# BW1098FFC_Connector.net
KiCad netlist of a schematic drawn in Altium Designer
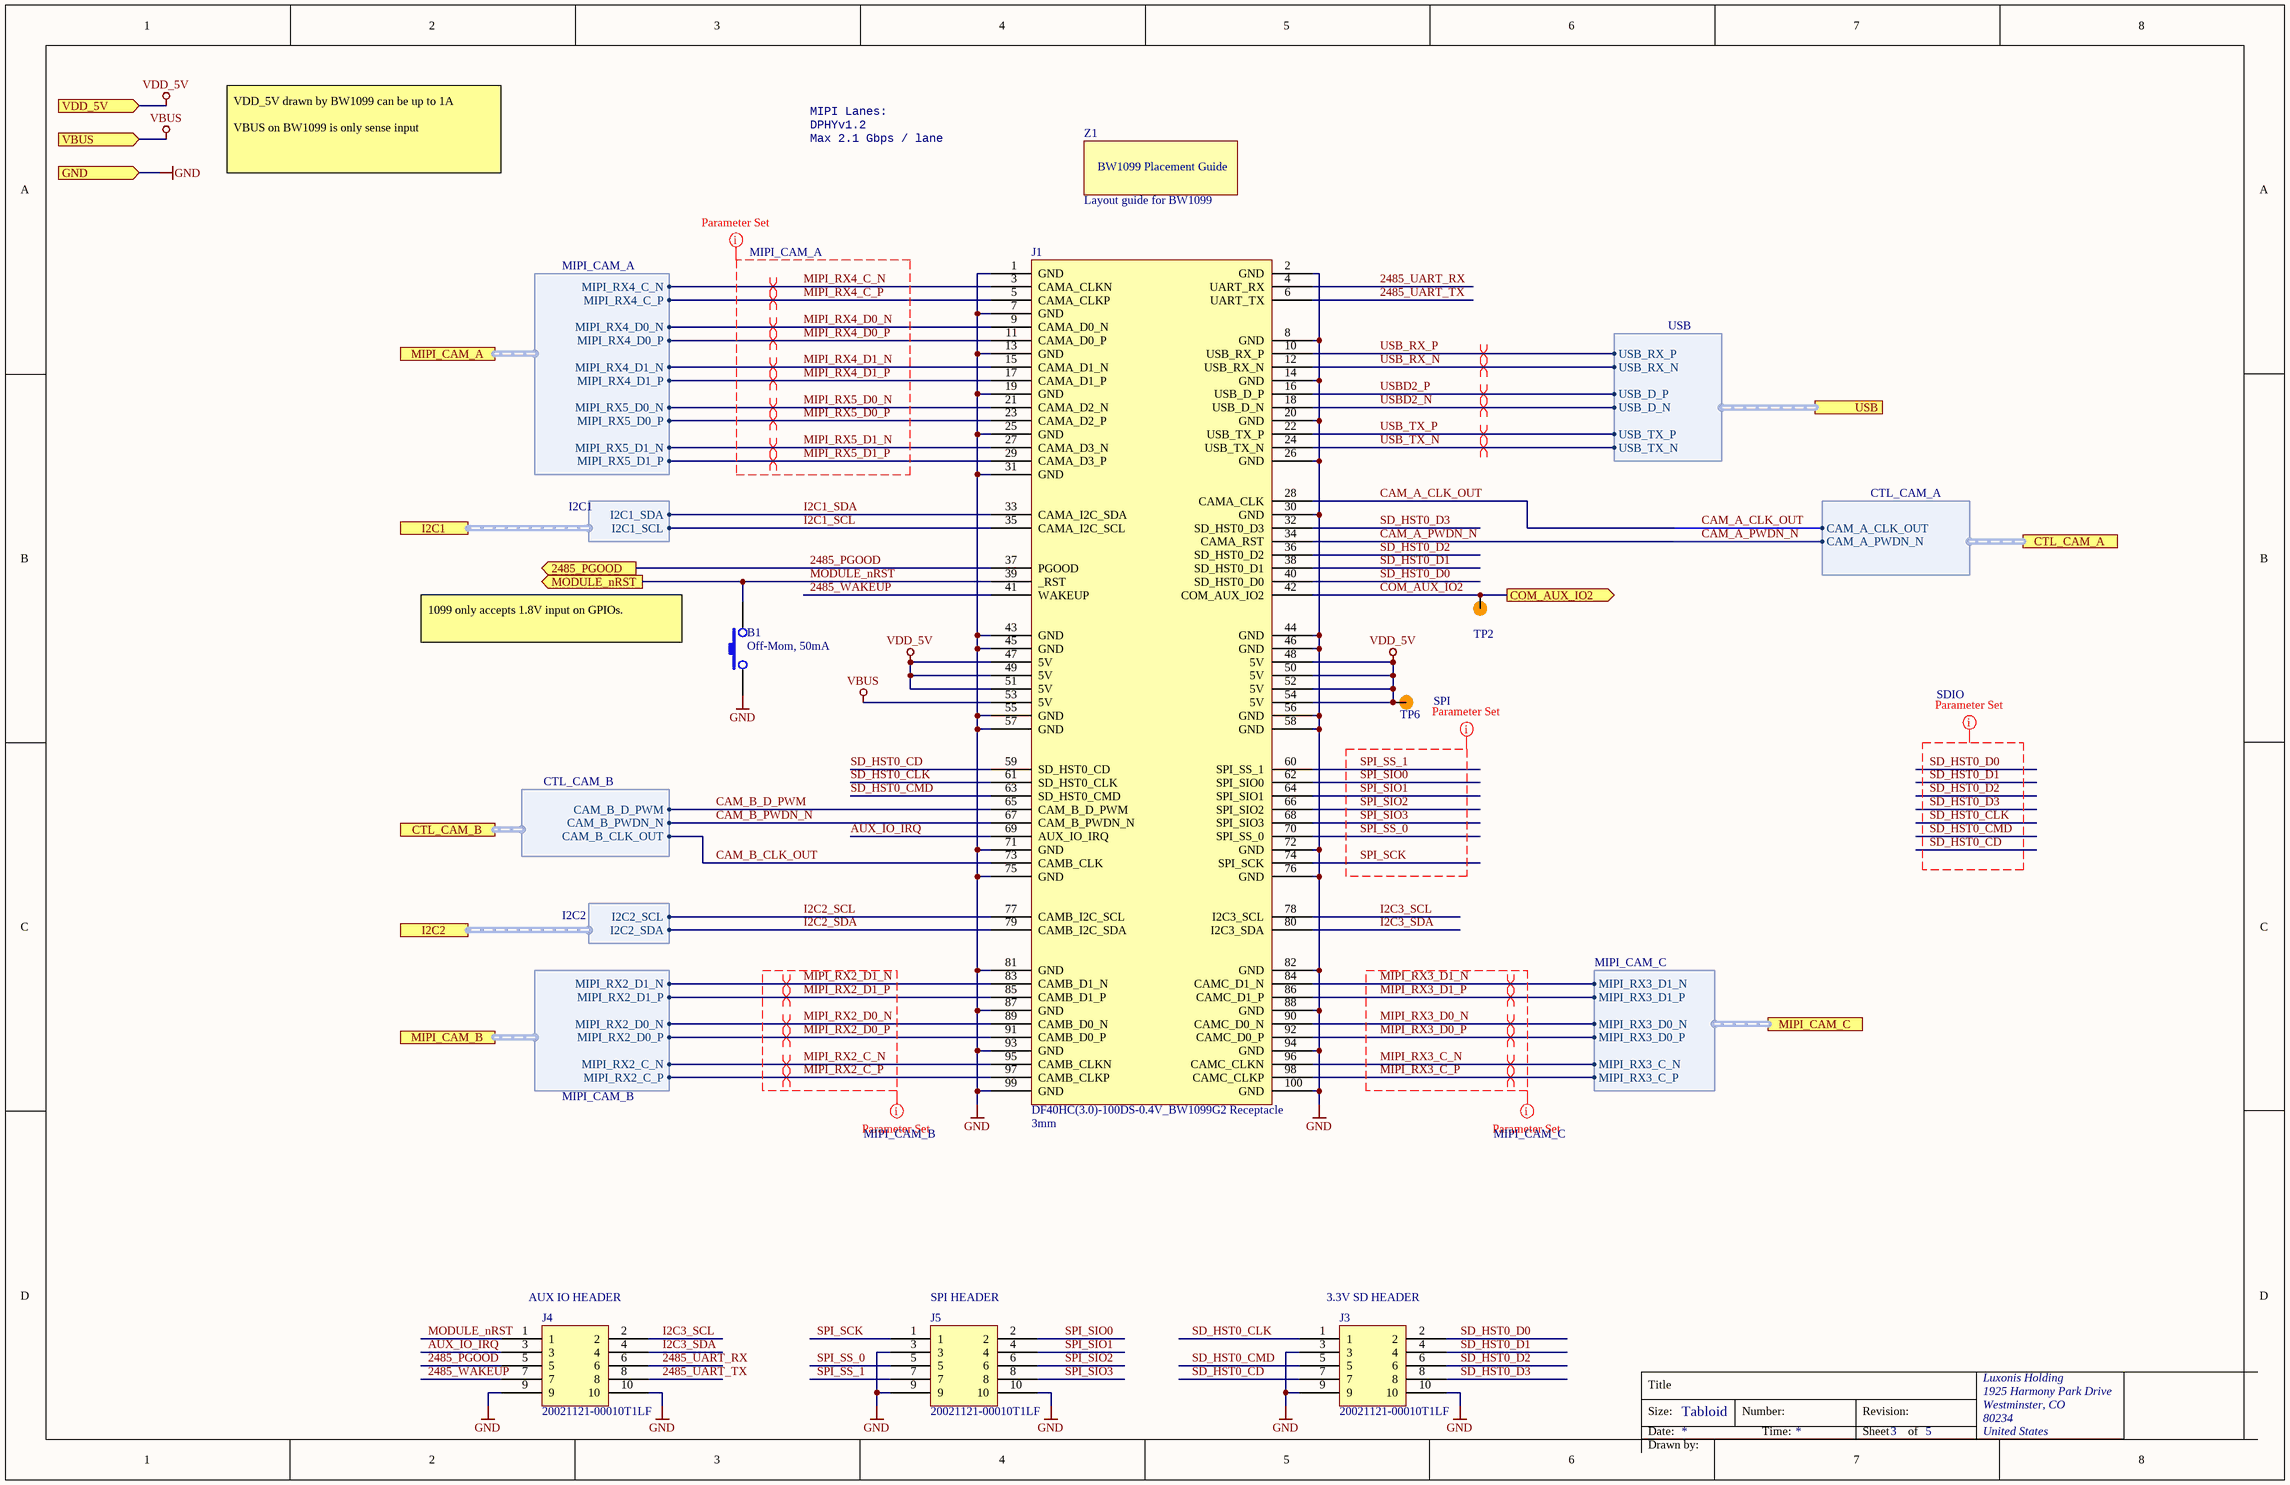
[diagram p0: BW1098FFC_Connector.SchDoc]

(export (version "E")
  (design (tool "Eeschema 10.0.6"))
  (components
    (comp (ref "B1")
      (value "Off-Mom, 50mA")
      (footprint "LuxonisMaster:DTSM-32N-V")
      (description "SWITCH TACTILE SMT 3.5mm * 6mm , brown 160gf")
      (libsource (lib "LuxonisMaster") (part "DTSM-32N-V"))
    )
    (comp (ref "J1")
      (value "DF40HC(3.0)-100DS-0.4V_BW1099G2 Receptacle")
      (footprint "LuxonisMaster:DF40HC-3.0-100DS-0.4V_minpad")
      (description "CONN RCPT 100POS 0.4MM SMD GOLD")
      (fields (field (name "MATED STACKING HEIGHT") "3mm"))
      (libsource (lib "LuxonisMaster") (part "DF40HC(3.0)-100DS-0.4V_BW1099_G2"))
    )
    (comp (ref "J3")
      (value "20021121-00010T1LF")
      (footprint "LuxonisMaster:20021121-00010T1LF")
      (description "CONN HEADER SMD 10POS 1.27MM")
      (libsource (lib "LuxonisMaster") (part "20021121-00010T1LF"))
    )
    (comp (ref "J4")
      (value "20021121-00010T1LF")
      (footprint "LuxonisMaster:20021121-00010T1LF")
      (description "CONN HEADER SMD 10POS 1.27MM")
      (libsource (lib "LuxonisMaster") (part "20021121-00010T1LF"))
    )
    (comp (ref "J5")
      (value "20021121-00010T1LF")
      (footprint "LuxonisMaster:20021121-00010T1LF")
      (description "CONN HEADER SMD 10POS 1.27MM")
      (libsource (lib "LuxonisMaster") (part "20021121-00010T1LF"))
    )
    (comp (ref "TP2")
      (value "TP100_200_NS")
      (footprint "LuxonisMaster:TP100_200_NS")
      (libsource (lib "LuxonisMaster") (part "TEST_POINT"))
    )
    (comp (ref "TP6")
      (value "TP100_200_NS")
      (footprint "LuxonisMaster:TP100_200_NS")
      (libsource (lib "LuxonisMaster") (part "TEST_POINT"))
    )
    (comp (ref "Z1")
      (value "Layout guide for BW1099")
      (footprint "LuxonisMaster:BW1099_Footprint")
      (description "MISC - Use for aligning BW1099 mount")
      (libsource (lib "LuxonisMaster") (part "BW1099_Footprint"))
    )
  )
  (nets
    (net (code "9") (name "/2485_PGOOD") (class "Default")
      (node (ref "J1") (pin "37") (pinfunction "PGOOD_37") (pintype "passive"))
      (node (ref "J4") (pin "5") (pinfunction "5_5") (pintype "passive"))
    )
    (net (code "10") (name "/2485_UART_RX") (class "Default")
      (node (ref "J1") (pin "4") (pinfunction "UART_RX_4") (pintype "passive"))
      (node (ref "J4") (pin "6") (pinfunction "6_6") (pintype "passive"))
    )
    (net (code "11") (name "/2485_UART_TX") (class "Default")
      (node (ref "J1") (pin "6") (pinfunction "UART_TX_6") (pintype "passive"))
      (node (ref "J4") (pin "8") (pinfunction "8_8") (pintype "passive"))
    )
    (net (code "12") (name "/2485_WAKEUP") (class "Default")
      (node (ref "J1") (pin "41") (pinfunction "WAKEUP_41") (pintype "passive"))
      (node (ref "J4") (pin "7") (pinfunction "7_7") (pintype "passive"))
    )
    (net (code "13") (name "/AUX_IO_IRQ") (class "Default")
      (node (ref "J1") (pin "69") (pinfunction "AUX_IO_IRQ_69") (pintype "passive"))
      (node (ref "J4") (pin "3") (pinfunction "3_3") (pintype "passive"))
    )
    (net (code "14") (name "/CAM_A_CLK_OUT") (class "Default")
      (node (ref "J1") (pin "28") (pinfunction "CAMA_CLK_28") (pintype "passive"))
    )
    (net (code "15") (name "/CAM_A_PWDN_N") (class "Default")
      (node (ref "J1") (pin "34") (pinfunction "CAMA_RST_34") (pintype "passive"))
    )
    (net (code "16") (name "/CAM_B_CLK_OUT") (class "Default")
      (node (ref "J1") (pin "73") (pinfunction "CAMB_CLK_73") (pintype "passive"))
    )
    (net (code "17") (name "/CAM_B_D_PWM") (class "Default")
      (node (ref "J1") (pin "65") (pinfunction "CAM_B_D_PWM_65") (pintype "passive"))
    )
    (net (code "18") (name "/CAM_B_PWDN_N") (class "Default")
      (node (ref "J1") (pin "67") (pinfunction "CAM_B_PWDN_N_67") (pintype "passive"))
    )
    (net (code "19") (name "/COM_AUX_IO2") (class "Default")
      (node (ref "J1") (pin "42") (pinfunction "COM_AUX_IO2_42") (pintype "passive"))
      (node (ref "TP2") (pin "1") (pintype "passive"))
    )
    (net (code "20") (name "/I2C1_SCL") (class "Default")
      (node (ref "J1") (pin "35") (pinfunction "CAMA_I2C_SCL_35") (pintype "passive"))
    )
    (net (code "21") (name "/I2C1_SDA") (class "Default")
      (node (ref "J1") (pin "33") (pinfunction "CAMA_I2C_SDA_33") (pintype "passive"))
    )
    (net (code "22") (name "/I2C2_SCL") (class "Default")
      (node (ref "J1") (pin "77") (pinfunction "CAMB_I2C_SCL_77") (pintype "passive"))
    )
    (net (code "23") (name "/I2C2_SDA") (class "Default")
      (node (ref "J1") (pin "79") (pinfunction "CAMB_I2C_SDA_79") (pintype "passive"))
    )
    (net (code "24") (name "/I2C3_SCL") (class "Default")
      (node (ref "J1") (pin "78") (pinfunction "I2C3_SCL_78") (pintype "passive"))
      (node (ref "J4") (pin "2") (pinfunction "2_2") (pintype "passive"))
    )
    (net (code "25") (name "/I2C3_SDA") (class "Default")
      (node (ref "J1") (pin "80") (pinfunction "I2C3_SDA_80") (pintype "passive"))
      (node (ref "J4") (pin "4") (pinfunction "4_4") (pintype "passive"))
    )
    (net (code "26") (name "/MIPI_RX2_C_N") (class "Default")
      (node (ref "J1") (pin "95") (pinfunction "CAMB_CLKN_95") (pintype "passive"))
    )
    (net (code "27") (name "/MIPI_RX2_C_P") (class "Default")
      (node (ref "J1") (pin "97") (pinfunction "CAMB_CLKP_97") (pintype "passive"))
    )
    (net (code "28") (name "/MIPI_RX2_D0_N") (class "Default")
      (node (ref "J1") (pin "89") (pinfunction "CAMB_D0_N_89") (pintype "passive"))
    )
    (net (code "29") (name "/MIPI_RX2_D0_P") (class "Default")
      (node (ref "J1") (pin "91") (pinfunction "CAMB_D0_P_91") (pintype "passive"))
    )
    (net (code "30") (name "/MIPI_RX2_D1_N") (class "Default")
      (node (ref "J1") (pin "83") (pinfunction "CAMB_D1_N_83") (pintype "passive"))
    )
    (net (code "31") (name "/MIPI_RX2_D1_P") (class "Default")
      (node (ref "J1") (pin "85") (pinfunction "CAMB_D1_P_85") (pintype "passive"))
    )
    (net (code "32") (name "/MIPI_RX3_C_N") (class "Default")
      (node (ref "J1") (pin "96") (pinfunction "CAMC_CLKN_96") (pintype "passive"))
    )
    (net (code "33") (name "/MIPI_RX3_C_P") (class "Default")
      (node (ref "J1") (pin "98") (pinfunction "CAMC_CLKP_98") (pintype "passive"))
    )
    (net (code "34") (name "/MIPI_RX3_D0_N") (class "Default")
      (node (ref "J1") (pin "90") (pinfunction "CAMC_D0_N_90") (pintype "passive"))
    )
    (net (code "35") (name "/MIPI_RX3_D0_P") (class "Default")
      (node (ref "J1") (pin "92") (pinfunction "CAMC_D0_P_92") (pintype "passive"))
    )
    (net (code "36") (name "/MIPI_RX3_D1_N") (class "Default")
      (node (ref "J1") (pin "84") (pinfunction "CAMC_D1_N_84") (pintype "passive"))
    )
    (net (code "37") (name "/MIPI_RX3_D1_P") (class "Default")
      (node (ref "J1") (pin "86") (pinfunction "CAMC_D1_P_86") (pintype "passive"))
    )
    (net (code "38") (name "/MIPI_RX4_C_N") (class "Default")
      (node (ref "J1") (pin "3") (pinfunction "CAMA_CLKN_3") (pintype "passive"))
    )
    (net (code "39") (name "/MIPI_RX4_C_P") (class "Default")
      (node (ref "J1") (pin "5") (pinfunction "CAMA_CLKP_5") (pintype "passive"))
    )
    (net (code "40") (name "/MIPI_RX4_D0_N") (class "Default")
      (node (ref "J1") (pin "9") (pinfunction "CAMA_D0_N_9") (pintype "passive"))
    )
    (net (code "41") (name "/MIPI_RX4_D0_P") (class "Default")
      (node (ref "J1") (pin "11") (pinfunction "CAMA_D0_P_11") (pintype "passive"))
    )
    (net (code "42") (name "/MIPI_RX4_D1_N") (class "Default")
      (node (ref "J1") (pin "15") (pinfunction "CAMA_D1_N_15") (pintype "passive"))
    )
    (net (code "43") (name "/MIPI_RX4_D1_P") (class "Default")
      (node (ref "J1") (pin "17") (pinfunction "CAMA_D1_P_17") (pintype "passive"))
    )
    (net (code "44") (name "/MIPI_RX5_D0_N") (class "Default")
      (node (ref "J1") (pin "21") (pinfunction "CAMA_D2_N_21") (pintype "passive"))
    )
    (net (code "45") (name "/MIPI_RX5_D0_P") (class "Default")
      (node (ref "J1") (pin "23") (pinfunction "CAMA_D2_P_23") (pintype "passive"))
    )
    (net (code "46") (name "/MIPI_RX5_D1_N") (class "Default")
      (node (ref "J1") (pin "27") (pinfunction "CAMA_D3_N_27") (pintype "passive"))
    )
    (net (code "47") (name "/MIPI_RX5_D1_P") (class "Default")
      (node (ref "J1") (pin "29") (pinfunction "CAMA_D3_P_29") (pintype "passive"))
    )
    (net (code "48") (name "/MODULE_nRST") (class "Default")
      (node (ref "B1") (pin "2") (pinfunction "2_2") (pintype "passive"))
      (node (ref "J1") (pin "39") (pinfunction "_RST_39") (pintype "passive"))
      (node (ref "J4") (pin "1") (pinfunction "1_1") (pintype "passive"))
    )
    (net (code "49") (name "/SD_HST0_CD") (class "Default")
      (node (ref "J1") (pin "59") (pinfunction "SD_HST0_CD_59") (pintype "passive"))
      (node (ref "J3") (pin "7") (pinfunction "7_7") (pintype "passive"))
    )
    (net (code "50") (name "/SD_HST0_CLK") (class "Default")
      (node (ref "J1") (pin "61") (pinfunction "SD_HST0_CLK_61") (pintype "passive"))
      (node (ref "J3") (pin "1") (pinfunction "1_1") (pintype "passive"))
    )
    (net (code "51") (name "/SD_HST0_CMD") (class "Default")
      (node (ref "J1") (pin "63") (pinfunction "SD_HST0_CMD_63") (pintype "passive"))
      (node (ref "J3") (pin "5") (pinfunction "5_5") (pintype "passive"))
    )
    (net (code "52") (name "/SD_HST0_D0") (class "Default")
      (node (ref "J1") (pin "40") (pinfunction "SD_HST0_D0_40") (pintype "passive"))
      (node (ref "J3") (pin "2") (pinfunction "2_2") (pintype "passive"))
    )
    (net (code "53") (name "/SD_HST0_D1") (class "Default")
      (node (ref "J1") (pin "38") (pinfunction "SD_HST0_D1_38") (pintype "passive"))
      (node (ref "J3") (pin "4") (pinfunction "4_4") (pintype "passive"))
    )
    (net (code "54") (name "/SD_HST0_D2") (class "Default")
      (node (ref "J1") (pin "36") (pinfunction "SD_HST0_D2_36") (pintype "passive"))
      (node (ref "J3") (pin "6") (pinfunction "6_6") (pintype "passive"))
    )
    (net (code "55") (name "/SD_HST0_D3") (class "Default")
      (node (ref "J1") (pin "32") (pinfunction "SD_HST0_D3_32") (pintype "passive"))
      (node (ref "J3") (pin "8") (pinfunction "8_8") (pintype "passive"))
    )
    (net (code "56") (name "/SPI_SCK") (class "Default")
      (node (ref "J1") (pin "74") (pinfunction "SPI_SCK_74") (pintype "passive"))
      (node (ref "J5") (pin "1") (pinfunction "1_1") (pintype "passive"))
    )
    (net (code "57") (name "/SPI_SIO0") (class "Default")
      (node (ref "J1") (pin "62") (pinfunction "SPI_SIO0_62") (pintype "passive"))
      (node (ref "J5") (pin "2") (pinfunction "2_2") (pintype "passive"))
    )
    (net (code "58") (name "/SPI_SIO1") (class "Default")
      (node (ref "J1") (pin "64") (pinfunction "SPI_SIO1_64") (pintype "passive"))
      (node (ref "J5") (pin "4") (pinfunction "4_4") (pintype "passive"))
    )
    (net (code "59") (name "/SPI_SIO2") (class "Default")
      (node (ref "J1") (pin "66") (pinfunction "SPI_SIO2_66") (pintype "passive"))
      (node (ref "J5") (pin "6") (pinfunction "6_6") (pintype "passive"))
    )
    (net (code "60") (name "/SPI_SIO3") (class "Default")
      (node (ref "J1") (pin "68") (pinfunction "SPI_SIO3_68") (pintype "passive"))
      (node (ref "J5") (pin "8") (pinfunction "8_8") (pintype "passive"))
    )
    (net (code "61") (name "/SPI_SS_0") (class "Default")
      (node (ref "J1") (pin "70") (pinfunction "SPI_SS_0_70") (pintype "passive"))
      (node (ref "J5") (pin "5") (pinfunction "5_5") (pintype "passive"))
    )
    (net (code "62") (name "/SPI_SS_1") (class "Default")
      (node (ref "J1") (pin "60") (pinfunction "SPI_SS_1_60") (pintype "passive"))
      (node (ref "J5") (pin "7") (pinfunction "7_7") (pintype "passive"))
    )
    (net (code "63") (name "/USBD2_N") (class "Default")
      (node (ref "J1") (pin "18") (pinfunction "USB_D_N_18") (pintype "passive"))
    )
    (net (code "64") (name "/USBD2_P") (class "Default")
      (node (ref "J1") (pin "16") (pinfunction "USB_D_P_16") (pintype "passive"))
    )
    (net (code "65") (name "/USB_RX_N") (class "Default")
      (node (ref "J1") (pin "12") (pinfunction "USB_RX_N_12") (pintype "passive"))
    )
    (net (code "66") (name "/USB_RX_P") (class "Default")
      (node (ref "J1") (pin "10") (pinfunction "USB_RX_P_10") (pintype "passive"))
    )
    (net (code "67") (name "/USB_TX_N") (class "Default")
      (node (ref "J1") (pin "24") (pinfunction "USB_TX_N_24") (pintype "passive"))
    )
    (net (code "68") (name "/USB_TX_P") (class "Default")
      (node (ref "J1") (pin "22") (pinfunction "USB_TX_P_22") (pintype "passive"))
    )
    (net (code "77") (name "GND") (class "Default")
      (node (ref "B1") (pin "1") (pinfunction "1_1") (pintype "passive"))
      (node (ref "J1") (pin "1") (pinfunction "GND_1") (pintype "passive"))
      (node (ref "J1") (pin "100") (pinfunction "GND_100") (pintype "passive"))
      (node (ref "J1") (pin "13") (pinfunction "GND_13") (pintype "passive"))
      (node (ref "J1") (pin "14") (pinfunction "GND_14") (pintype "passive"))
      (node (ref "J1") (pin "19") (pinfunction "GND_19") (pintype "passive"))
      (node (ref "J1") (pin "2") (pinfunction "GND_2") (pintype "passive"))
      (node (ref "J1") (pin "20") (pinfunction "GND_20") (pintype "passive"))
      (node (ref "J1") (pin "25") (pinfunction "GND_25") (pintype "passive"))
      (node (ref "J1") (pin "26") (pinfunction "GND_26") (pintype "passive"))
      (node (ref "J1") (pin "30") (pinfunction "GND_30") (pintype "passive"))
      (node (ref "J1") (pin "31") (pinfunction "GND_31") (pintype "passive"))
      (node (ref "J1") (pin "43") (pinfunction "GND_43") (pintype "passive"))
      (node (ref "J1") (pin "44") (pinfunction "GND_44") (pintype "passive"))
      (node (ref "J1") (pin "45") (pinfunction "GND_45") (pintype "passive"))
      (node (ref "J1") (pin "46") (pinfunction "GND_46") (pintype "passive"))
      (node (ref "J1") (pin "55") (pinfunction "GND_55") (pintype "passive"))
      (node (ref "J1") (pin "56") (pinfunction "GND_56") (pintype "passive"))
      (node (ref "J1") (pin "57") (pinfunction "GND_57") (pintype "passive"))
      (node (ref "J1") (pin "58") (pinfunction "GND_58") (pintype "passive"))
      (node (ref "J1") (pin "7") (pinfunction "GND_7") (pintype "passive"))
      (node (ref "J1") (pin "71") (pinfunction "GND_71") (pintype "passive"))
      (node (ref "J1") (pin "72") (pinfunction "GND_72") (pintype "passive"))
      (node (ref "J1") (pin "75") (pinfunction "GND_75") (pintype "passive"))
      (node (ref "J1") (pin "76") (pinfunction "GND_76") (pintype "passive"))
      (node (ref "J1") (pin "8") (pinfunction "GND_8") (pintype "passive"))
      (node (ref "J1") (pin "81") (pinfunction "GND_81") (pintype "passive"))
      (node (ref "J1") (pin "82") (pinfunction "GND_82") (pintype "passive"))
      (node (ref "J1") (pin "87") (pinfunction "GND_87") (pintype "passive"))
      (node (ref "J1") (pin "88") (pinfunction "GND_88") (pintype "passive"))
      (node (ref "J1") (pin "93") (pinfunction "GND_93") (pintype "passive"))
      (node (ref "J1") (pin "94") (pinfunction "GND_94") (pintype "passive"))
      (node (ref "J1") (pin "99") (pinfunction "GND_99") (pintype "passive"))
      (node (ref "J3") (pin "10") (pinfunction "10_10") (pintype "passive"))
      (node (ref "J3") (pin "3") (pinfunction "3_3") (pintype "passive"))
      (node (ref "J3") (pin "9") (pinfunction "9_9") (pintype "passive"))
      (node (ref "J4") (pin "10") (pinfunction "10_10") (pintype "passive"))
      (node (ref "J4") (pin "9") (pinfunction "9_9") (pintype "passive"))
      (node (ref "J5") (pin "10") (pinfunction "10_10") (pintype "passive"))
      (node (ref "J5") (pin "3") (pinfunction "3_3") (pintype "passive"))
      (node (ref "J5") (pin "9") (pinfunction "9_9") (pintype "passive"))
    )
    (net (code "78") (name "VBUS") (class "Default")
      (node (ref "J1") (pin "53") (pinfunction "5V_53") (pintype "passive"))
    )
    (net (code "79") (name "VDD_5V") (class "Default")
      (node (ref "J1") (pin "47") (pinfunction "5V_47") (pintype "passive"))
      (node (ref "J1") (pin "48") (pinfunction "5V_48") (pintype "passive"))
      (node (ref "J1") (pin "49") (pinfunction "5V_49") (pintype "passive"))
      (node (ref "J1") (pin "50") (pinfunction "5V_50") (pintype "passive"))
      (node (ref "J1") (pin "51") (pinfunction "5V_51") (pintype "passive"))
      (node (ref "J1") (pin "52") (pinfunction "5V_52") (pintype "passive"))
      (node (ref "J1") (pin "54") (pinfunction "5V_54") (pintype "passive"))
      (node (ref "TP6") (pin "1") (pintype "passive"))
    )
  )
)
